# openevse-ac-filter-v1_0.net
KiCad netlist of a schematic drawn in EAGLE
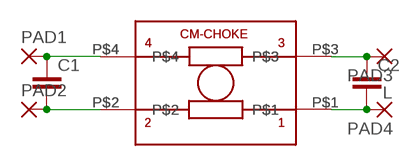
[diagram p0: schematic, sheet 1]

(export (version "E")
  (design (tool "Eeschema 10.0.6"))
  (components
    (comp (ref "C1")
      (value "C5/2.5")
      (footprint "eagle-import:C5B2.5")
      (libsource (lib "eagle-import") (part "C5/2.5"))
    )
    (comp (ref "C2")
      (value "C5/2.5")
      (footprint "eagle-import:C5B2.5")
      (libsource (lib "eagle-import") (part "C5/2.5"))
    )
    (comp (ref "PAD1")
      (value "2,54/0,9")
      (footprint "eagle-import:2,54_0,9")
      (libsource (lib "eagle-import") (part "2,54/0,9"))
    )
    (comp (ref "PAD2")
      (value "2,54/0,9")
      (footprint "eagle-import:2,54_0,9")
      (libsource (lib "eagle-import") (part "2,54/0,9"))
    )
    (comp (ref "PAD3")
      (value "2,54/0,9")
      (footprint "eagle-import:2,54_0,9")
      (libsource (lib "eagle-import") (part "2,54/0,9"))
    )
    (comp (ref "PAD4")
      (value "L")
      (footprint "eagle-import:2,54_0,9")
      (libsource (lib "eagle-import") (part "2,54/0,9"))
    )
    (comp (ref "U$1")
      (value "47mH")
      (footprint "eagle-import:RN114-0.3-02-47M")
      (libsource (lib "eagle-import") (part "RN114-0.3-02-47M"))
    )
    (comp (ref "U$2")
      (value "RN214-0.3-02-47M")
      (footprint "eagle-import:RN214-0.3-02-47M")
      (libsource (lib "eagle-import") (part "RN214-0.3-02-47M"))
    )
  )
  (nets
    (net (code "1") (name "Net-(PAD1-P)") (class "Default")
      (node (ref "C1") (pin "1") (pinfunction "1_1") (pintype "passive"))
      (node (ref "PAD1") (pin "1") (pinfunction "P_1") (pintype "passive"))
      (node (ref "U$1") (pin "P$4") (pinfunction "P$4_P$4") (pintype "bidirectional"))
      (node (ref "U$2") (pin "P$4") (pinfunction "P$4_P$4") (pintype "bidirectional"))
    )
    (net (code "2") (name "Net-(PAD2-P)") (class "Default")
      (node (ref "C1") (pin "2") (pinfunction "2_2") (pintype "passive"))
      (node (ref "PAD2") (pin "1") (pinfunction "P_1") (pintype "passive"))
      (node (ref "U$1") (pin "P$2") (pinfunction "P$2_P$2") (pintype "bidirectional"))
      (node (ref "U$2") (pin "P$2") (pinfunction "P$2_P$2") (pintype "bidirectional"))
    )
    (net (code "3") (name "Net-(PAD3-P)") (class "Default")
      (node (ref "C2") (pin "1") (pinfunction "1_1") (pintype "passive"))
      (node (ref "PAD3") (pin "1") (pinfunction "P_1") (pintype "passive"))
      (node (ref "U$1") (pin "P$3") (pinfunction "P$3_P$3") (pintype "bidirectional"))
      (node (ref "U$2") (pin "P$3") (pinfunction "P$3_P$3") (pintype "bidirectional"))
    )
    (net (code "4") (name "Net-(PAD4-P)") (class "Default")
      (node (ref "C2") (pin "2") (pinfunction "2_2") (pintype "passive"))
      (node (ref "PAD4") (pin "1") (pinfunction "P_1") (pintype "passive"))
      (node (ref "U$1") (pin "P$1") (pinfunction "P$1_P$1") (pintype "bidirectional"))
      (node (ref "U$2") (pin "P$1") (pinfunction "P$1_P$1") (pintype "bidirectional"))
    )
  )
)
